# main.net
KiCad netlist of a schematic drawn in EAGLE
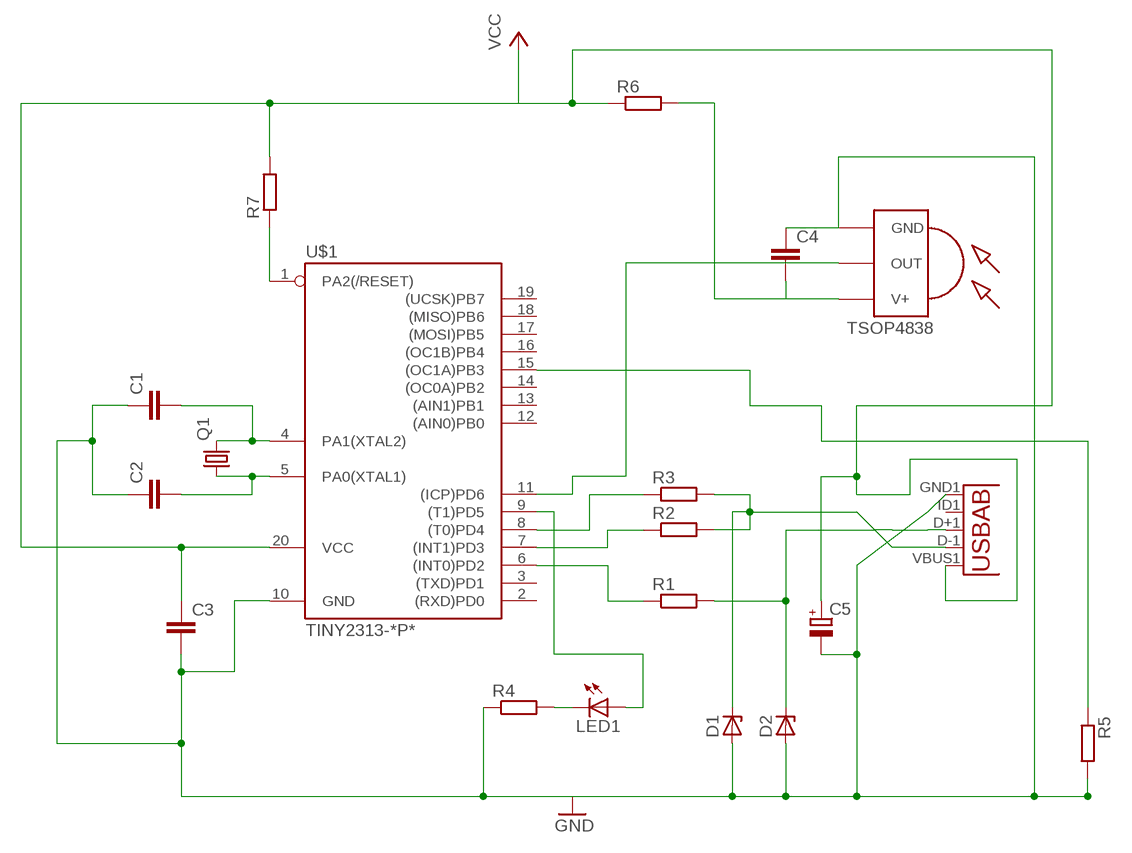
[diagram p0: schematic, sheet 1]

(export (version "E")
  (design (tool "Eeschema 10.0.6"))
  (components
    (comp (ref "C1")
      (value "C-EUC0603")
      (footprint "eagle-import:C0603")
      (libsource (lib "eagle-import") (part "C-EUC0603"))
    )
    (comp (ref "C2")
      (value "C-EUC0603")
      (footprint "eagle-import:C0603")
      (libsource (lib "eagle-import") (part "C-EUC0603"))
    )
    (comp (ref "C3")
      (value "C-EUC0603")
      (footprint "eagle-import:C0603")
      (libsource (lib "eagle-import") (part "C-EUC0603"))
    )
    (comp (ref "C4")
      (value "C-EUC0603")
      (footprint "eagle-import:C0603")
      (libsource (lib "eagle-import") (part "C-EUC0603"))
    )
    (comp (ref "C5")
      (value "CPOL-EUE2.5-6")
      (footprint "eagle-import:E2,5-6")
      (libsource (lib "eagle-import") (part "CPOL-EUE2.5-6"))
    )
    (comp (ref "D1")
      (value "ZENER-DIODESOD80C")
      (footprint "eagle-import:SOD80C")
      (libsource (lib "eagle-import") (part "ZENER-DIODESOD80C"))
    )
    (comp (ref "D2")
      (value "ZENER-DIODESOD80C")
      (footprint "eagle-import:SOD80C")
      (libsource (lib "eagle-import") (part "ZENER-DIODESOD80C"))
    )
    (comp (ref "LED1")
      (value "LED3MM")
      (footprint "eagle-import:LED3MM")
      (libsource (lib "eagle-import") (part "LED3MM"))
    )
    (comp (ref "Q1")
      (value "CRYSTALHC49U70")
      (footprint "eagle-import:HC49U70")
      (libsource (lib "eagle-import") (part "CRYSTALHC49U70"))
    )
    (comp (ref "R1")
      (value "R-EU_R0805")
      (footprint "eagle-import:R0805")
      (libsource (lib "eagle-import") (part "R-EU_R0805"))
    )
    (comp (ref "R2")
      (value "R-EU_R0603")
      (footprint "eagle-import:R0603")
      (libsource (lib "eagle-import") (part "R-EU_R0603"))
    )
    (comp (ref "R3")
      (value "R-EU_R0805")
      (footprint "eagle-import:R0805")
      (libsource (lib "eagle-import") (part "R-EU_R0805"))
    )
    (comp (ref "R4")
      (value "R-EU_R0603")
      (footprint "eagle-import:R0603")
      (libsource (lib "eagle-import") (part "R-EU_R0603"))
    )
    (comp (ref "R5")
      (value "R-EU_R0603")
      (footprint "eagle-import:R0603")
      (libsource (lib "eagle-import") (part "R-EU_R0603"))
    )
    (comp (ref "R6")
      (value "R-EU_R0603")
      (footprint "eagle-import:R0603")
      (libsource (lib "eagle-import") (part "R-EU_R0603"))
    )
    (comp (ref "R7")
      (value "R-EU_R0603")
      (footprint "eagle-import:R0603")
      (libsource (lib "eagle-import") (part "R-EU_R0603"))
    )
    (comp (ref "U$1")
      (value "TINY2313-*P*")
      (footprint "eagle-import:DIL20")
      (libsource (lib "eagle-import") (part "TINY2313-P"))
    )
    (comp (ref "U$2")
      (value "TSOP4838")
      (footprint "eagle-import:TSOP18XX")
      (libsource (lib "eagle-import") (part "TSOP4838"))
    )
    (comp (ref "U1")
      (value "USB\"\"")
      (footprint "eagle-import:USB-MICRO-SMD")
      (libsource (lib "eagle-import") (part "USB{dblquote}{dblquote}"))
    )
  )
  (nets
    (net (code "1") (name "GND") (class "Default")
      (node (ref "C1") (pin "1") (pinfunction "1_1") (pintype "passive"))
      (node (ref "C2") (pin "1") (pinfunction "1_1") (pintype "passive"))
      (node (ref "C3") (pin "2") (pinfunction "2_2") (pintype "passive"))
      (node (ref "C4") (pin "1") (pinfunction "1_1") (pintype "passive"))
      (node (ref "C5") (pin "-") (pinfunction "-_-") (pintype "passive"))
      (node (ref "D1") (pin "A") (pinfunction "A_A") (pintype "passive"))
      (node (ref "D2") (pin "A") (pinfunction "A_A") (pintype "passive"))
      (node (ref "R4") (pin "1") (pinfunction "1_1") (pintype "passive"))
      (node (ref "R5") (pin "2") (pinfunction "2_2") (pintype "passive"))
      (node (ref "U$1") (pin "10") (pinfunction "GND_10") (pintype "power_in"))
      (node (ref "U$2") (pin "GND") (pinfunction "GND_GND") (pintype "bidirectional"))
      (node (ref "U1") (pin "GND1") (pinfunction "GND_GND1") (pintype "bidirectional"))
    )
    (net (code "2") (name "Net-(LED1-C)") (class "Default")
      (node (ref "LED1") (pin "K") (pinfunction "C_K") (pintype "passive"))
      (node (ref "R4") (pin "2") (pinfunction "2_2") (pintype "passive"))
    )
    (net (code "3") (name "Net-(U$1-(ICP)PD6)") (class "Default")
      (node (ref "U$1") (pin "11") (pinfunction "(ICP)PD6_11") (pintype "bidirectional"))
      (node (ref "U$2") (pin "OUT") (pinfunction "OUT_OUT") (pintype "bidirectional"))
    )
    (net (code "4") (name "Net-(U$1-(INT0)PD2)") (class "Default")
      (node (ref "R1") (pin "1") (pinfunction "1_1") (pintype "passive"))
      (node (ref "U$1") (pin "6") (pinfunction "(INT0)PD2_6") (pintype "bidirectional"))
    )
    (net (code "5") (name "Net-(U$1-(INT1)PD3)") (class "Default")
      (node (ref "R2") (pin "1") (pinfunction "1_1") (pintype "passive"))
      (node (ref "U$1") (pin "7") (pinfunction "(INT1)PD3_7") (pintype "bidirectional"))
    )
    (net (code "6") (name "Net-(U$1-(OC1A)PB3)") (class "Default")
      (node (ref "R5") (pin "1") (pinfunction "1_1") (pintype "passive"))
      (node (ref "U$1") (pin "15") (pinfunction "(OC1A)PB3_15") (pintype "bidirectional"))
    )
    (net (code "7") (name "Net-(U$1-(T0)PD4)") (class "Default")
      (node (ref "R3") (pin "1") (pinfunction "1_1") (pintype "passive"))
      (node (ref "U$1") (pin "8") (pinfunction "(T0)PD4_8") (pintype "bidirectional"))
    )
    (net (code "8") (name "Net-(U$1-(T1)PD5)") (class "Default")
      (node (ref "LED1") (pin "A") (pinfunction "A_A") (pintype "passive"))
      (node (ref "U$1") (pin "9") (pinfunction "(T1)PD5_9") (pintype "bidirectional"))
    )
    (net (code "9") (name "Net-(U$1-PA0(XTAL1))") (class "Default")
      (node (ref "C2") (pin "2") (pinfunction "2_2") (pintype "passive"))
      (node (ref "Q1") (pin "1") (pinfunction "1_1") (pintype "passive"))
      (node (ref "U$1") (pin "5") (pinfunction "PA0(XTAL1)_5") (pintype "bidirectional"))
    )
    (net (code "10") (name "Net-(U$1-PA1(XTAL2))") (class "Default")
      (node (ref "C1") (pin "2") (pinfunction "2_2") (pintype "passive"))
      (node (ref "Q1") (pin "2") (pinfunction "2_2") (pintype "passive"))
      (node (ref "U$1") (pin "4") (pinfunction "PA1(XTAL2)_4") (pintype "bidirectional"))
    )
    (net (code "11") (name "Net-(U$1-PA2({slash}RESET))") (class "Default")
      (node (ref "R7") (pin "1") (pinfunction "1_1") (pintype "passive"))
      (node (ref "U$1") (pin "1") (pinfunction "PA2(/RESET)_1") (pintype "input"))
    )
    (net (code "12") (name "Net-(U$2-V+)") (class "Default")
      (node (ref "C4") (pin "2") (pinfunction "2_2") (pintype "passive"))
      (node (ref "R6") (pin "2") (pinfunction "2_2") (pintype "passive"))
      (node (ref "U$2") (pin "VCC") (pinfunction "V+_VCC") (pintype "bidirectional"))
    )
    (net (code "13") (name "Net-(U1-D+)") (class "Default")
      (node (ref "D2") (pin "C") (pinfunction "C_C") (pintype "passive"))
      (node (ref "R1") (pin "2") (pinfunction "2_2") (pintype "passive"))
      (node (ref "U1") (pin "D+1") (pinfunction "D+_D+1") (pintype "bidirectional"))
    )
    (net (code "14") (name "Net-(U1-D-)") (class "Default")
      (node (ref "D1") (pin "C") (pinfunction "C_C") (pintype "passive"))
      (node (ref "R2") (pin "2") (pinfunction "2_2") (pintype "passive"))
      (node (ref "R3") (pin "2") (pinfunction "2_2") (pintype "passive"))
      (node (ref "U1") (pin "D-1") (pinfunction "D-_D-1") (pintype "bidirectional"))
    )
    (net (code "15") (name "VCC") (class "Default")
      (node (ref "C3") (pin "1") (pinfunction "1_1") (pintype "passive"))
      (node (ref "C5") (pin "+") (pinfunction "+_+") (pintype "passive"))
      (node (ref "R6") (pin "1") (pinfunction "1_1") (pintype "passive"))
      (node (ref "R7") (pin "2") (pinfunction "2_2") (pintype "passive"))
      (node (ref "U$1") (pin "20") (pinfunction "VCC_20") (pintype "power_in"))
      (node (ref "U1") (pin "VBUS1") (pinfunction "VBUS_VBUS1") (pintype "bidirectional"))
    )
    (net (code "16") (name "unconnected-(U$1-(AIN0)PB0-Pad12)") (class "Default")
      (node (ref "U$1") (pin "12") (pinfunction "(AIN0)PB0_12") (pintype "bidirectional"))
    )
    (net (code "17") (name "unconnected-(U$1-(AIN1)PB1-Pad13)") (class "Default")
      (node (ref "U$1") (pin "13") (pinfunction "(AIN1)PB1_13") (pintype "bidirectional"))
    )
    (net (code "18") (name "unconnected-(U$1-(MISO)PB6-Pad18)") (class "Default")
      (node (ref "U$1") (pin "18") (pinfunction "(MISO)PB6_18") (pintype "bidirectional"))
    )
    (net (code "19") (name "unconnected-(U$1-(MOSI)PB5-Pad17)") (class "Default")
      (node (ref "U$1") (pin "17") (pinfunction "(MOSI)PB5_17") (pintype "bidirectional"))
    )
    (net (code "20") (name "unconnected-(U$1-(OC0A)PB2-Pad14)") (class "Default")
      (node (ref "U$1") (pin "14") (pinfunction "(OC0A)PB2_14") (pintype "bidirectional"))
    )
    (net (code "21") (name "unconnected-(U$1-(OC1B)PB4-Pad16)") (class "Default")
      (node (ref "U$1") (pin "16") (pinfunction "(OC1B)PB4_16") (pintype "bidirectional"))
    )
    (net (code "22") (name "unconnected-(U$1-(RXD)PD0-Pad2)") (class "Default")
      (node (ref "U$1") (pin "2") (pinfunction "(RXD)PD0_2") (pintype "bidirectional"))
    )
    (net (code "23") (name "unconnected-(U$1-(TXD)PD1-Pad3)") (class "Default")
      (node (ref "U$1") (pin "3") (pinfunction "(TXD)PD1_3") (pintype "bidirectional"))
    )
    (net (code "24") (name "unconnected-(U$1-(UCSK)PB7-Pad19)") (class "Default")
      (node (ref "U$1") (pin "19") (pinfunction "(UCSK)PB7_19") (pintype "bidirectional"))
    )
    (net (code "25") (name "unconnected-(U1-USBID-PadID1)") (class "Default")
      (node (ref "U1") (pin "ID1") (pinfunction "USBID_ID1") (pintype "bidirectional"))
    )
  )
)
